# Precharge.net
KiCad netlist of a schematic drawn in Altium Designer
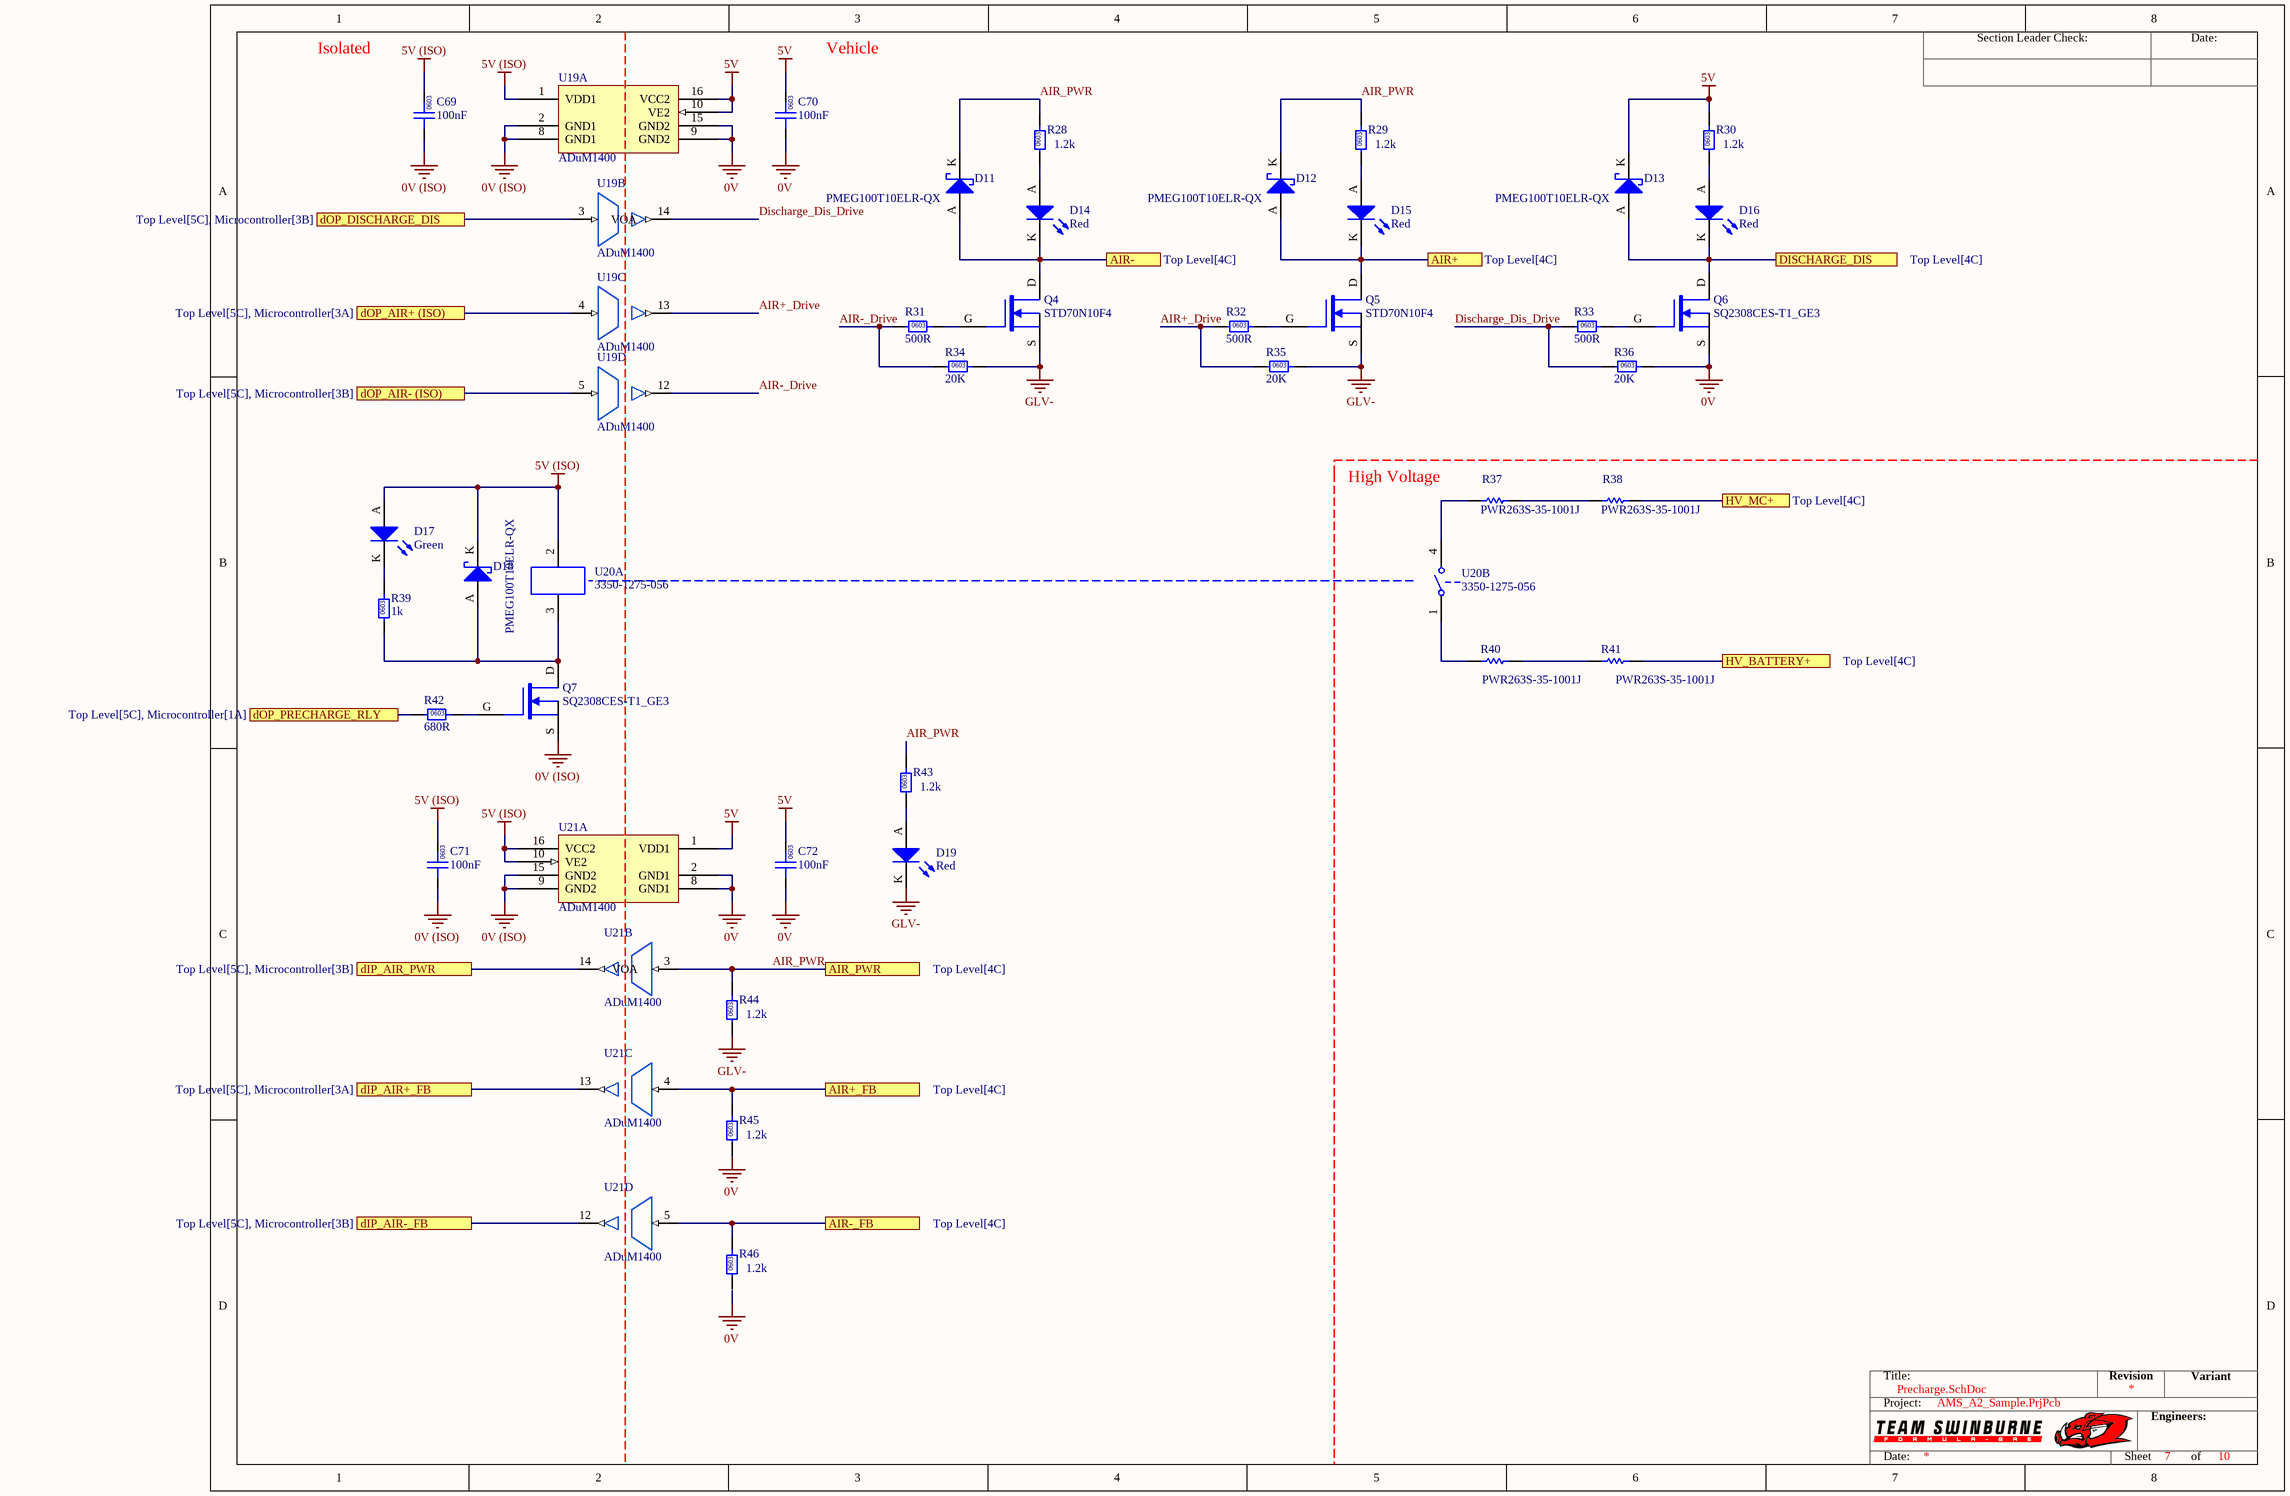
[diagram p0: Precharge.SchDoc]

(export (version "E")
  (design (tool "Eeschema 10.0.6"))
  (components
    (comp (ref "C69")
      (value "100nF")
      (footprint "0603")
      (fields
        (field (name "PART NUMBER") "GCM188L81H104KA57D")
        (field (name "MANUFACTURER") "muRata")
        (field (name "TOLERANCE") "±10%")
      )
      (libsource (lib "ts_standard_library") (part "Capacitor 0603"))
    )
    (comp (ref "C70")
      (value "100nF")
      (footprint "0603")
      (fields
        (field (name "PART NUMBER") "GCM188L81H104KA57D")
        (field (name "MANUFACTURER") "muRata")
        (field (name "TOLERANCE") "±10%")
      )
      (libsource (lib "ts_standard_library") (part "Capacitor 0603"))
    )
    (comp (ref "C71")
      (value "100nF")
      (footprint "0603")
      (fields
        (field (name "PART NUMBER") "GCM188L81H104KA57D")
        (field (name "MANUFACTURER") "muRata")
        (field (name "TOLERANCE") "±10%")
      )
      (libsource (lib "ts_standard_library") (part "Capacitor 0603"))
    )
    (comp (ref "C72")
      (value "100nF")
      (footprint "0603")
      (fields
        (field (name "PART NUMBER") "GCM188L81H104KA57D")
        (field (name "MANUFACTURER") "muRata")
        (field (name "TOLERANCE") "±10%")
      )
      (libsource (lib "ts_standard_library") (part "Capacitor 0603"))
    )
    (comp (ref "D11")
      (value "PMEG100T10ELR-QX")
      (footprint "NXP SOD123W")
      (fields
        (field (name "MANUFACTURER") "Nexperia USA Inc.")
        (field (name "DIGIKEY PART NUMBER") "1727-PMEG100T10ELR-QXCT-ND")
      )
      (libsource (lib "ts_standard_library") (part "Diode (Schottky)"))
    )
    (comp (ref "D12")
      (value "PMEG100T10ELR-QX")
      (footprint "NXP SOD123W")
      (fields
        (field (name "MANUFACTURER") "Nexperia USA Inc.")
        (field (name "DIGIKEY PART NUMBER") "1727-PMEG100T10ELR-QXCT-ND")
      )
      (libsource (lib "ts_standard_library") (part "Diode (Schottky)"))
    )
    (comp (ref "D13")
      (value "PMEG100T10ELR-QX")
      (footprint "NXP SOD123W")
      (fields
        (field (name "MANUFACTURER") "Nexperia USA Inc.")
        (field (name "DIGIKEY PART NUMBER") "1727-PMEG100T10ELR-QXCT-ND")
      )
      (libsource (lib "ts_standard_library") (part "Diode (Schottky)"))
    )
    (comp (ref "D14")
      (value "Red")
      (footprint "0805 LED")
      (description "Red LED Indication - Discrete 1.75V 0805 (2012 Metric)")
      (fields (field (name "PART NUMBER") "SML-210LTT86") (field (name "MANUFACTURER") "ROHM Semiconductor"))
      (libsource (lib "ts_standard_library") (part "LED"))
    )
    (comp (ref "D15")
      (value "Red")
      (footprint "0805 LED")
      (description "Red LED Indication - Discrete 1.75V 0805 (2012 Metric)")
      (fields (field (name "PART NUMBER") "SML-210LTT86") (field (name "MANUFACTURER") "ROHM Semiconductor"))
      (libsource (lib "ts_standard_library") (part "LED"))
    )
    (comp (ref "D16")
      (value "Red")
      (footprint "0805 LED")
      (description "Red LED Indication - Discrete 1.75V 0805 (2012 Metric)")
      (fields (field (name "PART NUMBER") "SML-210LTT86") (field (name "MANUFACTURER") "ROHM Semiconductor"))
      (libsource (lib "ts_standard_library") (part "LED"))
    )
    (comp (ref "D17")
      (value "Green")
      (footprint "0805 LED")
      (description "Green LED Indication - Discrete 1.75V 0805 (2012 Metric)")
      (fields (field (name "PART NUMBER") "SML-210FTT86") (field (name "MANUFACTURER") "ROHM Semiconductor"))
      (libsource (lib "ts_20-standard-library") (part "LED"))
    )
    (comp (ref "D18")
      (value "PMEG100T10ELR-QX")
      (footprint "NXP SOD123W")
      (fields
        (field (name "MANUFACTURER") "Nexperia USA Inc.")
        (field (name "DIGIKEY PART NUMBER") "1727-PMEG100T10ELR-QXCT-ND")
      )
      (libsource (lib "ts_standard_library") (part "Diode (Schottky)"))
    )
    (comp (ref "D19")
      (value "Red")
      (footprint "0805 LED")
      (description "Red LED Indication - Discrete 1.75V 0805 (2012 Metric)")
      (fields (field (name "PART NUMBER") "SML-210LTT86") (field (name "MANUFACTURER") "ROHM Semiconductor"))
      (libsource (lib "ts_standard_library") (part "LED"))
    )
    (comp (ref "Q4")
      (value "STD70N10F4")
      (footprint "STM TO-252 MOSFET")
      (description "N-Channel 100V 60A (Tc) 125W (Tc) Surface Mount DPAK")
      (fields
        (field (name "MANUFACTURER") "STMicroelectronics")
        (field (name "DIGIKEY PART NUMBER") "497-8806-2-ND")
        (field (name "PUBLISHER") "Altium Limited")
      )
      (libsource (lib "ts_standard_library") (part "MOSFET-N"))
    )
    (comp (ref "Q5")
      (value "STD70N10F4")
      (footprint "STM TO-252 MOSFET")
      (description "N-Channel 100V 60A (Tc) 125W (Tc) Surface Mount DPAK")
      (fields
        (field (name "MANUFACTURER") "STMicroelectronics")
        (field (name "DIGIKEY PART NUMBER") "497-8806-2-ND")
        (field (name "PUBLISHER") "Altium Limited")
      )
      (libsource (lib "ts_standard_library") (part "MOSFET-N"))
    )
    (comp (ref "Q6")
      (value "SQ2308CES-T1_GE3")
      (footprint "VSHY SOT-23-3")
      (description "MOSFET N-CH 60V 2.3A SOT23")
      (fields
        (field (name "MANUFACTURER") "Vishay Siliconix")
        (field (name "DIGIKEY PART NUMBER") "SQ2308CES-T1_GE3CT-ND")
        (field (name "PUBLISHER") "Altium Limited")
      )
      (libsource (lib "ts_standard_library") (part "MOSFET-N"))
    )
    (comp (ref "Q7")
      (value "SQ2308CES-T1_GE3")
      (footprint "VSHY SOT-23-3")
      (description "MOSFET N-CH 60V 2.3A SOT23")
      (fields
        (field (name "MANUFACTURER") "Vishay Siliconix")
        (field (name "DIGIKEY PART NUMBER") "SQ2308CES-T1_GE3CT-ND")
        (field (name "PUBLISHER") "Altium Limited")
      )
      (libsource (lib "ts_standard_library") (part "MOSFET-N"))
    )
    (comp (ref "R28")
      (value "1.2k")
      (footprint "0603")
      (fields
        (field (name "PART NUMBER") "RC0603JR-071K2L")
        (field (name "MANUFACTURER") "YAGEO")
        (field (name "TOLERANCE") "0.01")
      )
      (libsource (lib "ts_standard_library") (part "Resistor 0603"))
    )
    (comp (ref "R29")
      (value "1.2k")
      (footprint "0603")
      (fields
        (field (name "PART NUMBER") "RC0603JR-071K2L")
        (field (name "MANUFACTURER") "YAGEO")
        (field (name "TOLERANCE") "0.01")
      )
      (libsource (lib "ts_standard_library") (part "Resistor 0603"))
    )
    (comp (ref "R30")
      (value "1.2k")
      (footprint "0603")
      (fields
        (field (name "PART NUMBER") "RC0603JR-071K2L")
        (field (name "MANUFACTURER") "YAGEO")
        (field (name "TOLERANCE") "0.01")
      )
      (libsource (lib "ts_standard_library") (part "Resistor 0603"))
    )
    (comp (ref "R31")
      (value "500R")
      (footprint "0603")
      (fields
        (field (name "PART NUMBER") "RT0603BRD07500RL")
        (field (name "MANUFACTURER") "YAGEO")
        (field (name "TOLERANCE") "0.01")
      )
      (libsource (lib "ts_standard_library") (part "Resistor 0603"))
    )
    (comp (ref "R32")
      (value "500R")
      (footprint "0603")
      (fields
        (field (name "PART NUMBER") "RT0603BRD07500RL")
        (field (name "MANUFACTURER") "YAGEO")
        (field (name "TOLERANCE") "0.01")
      )
      (libsource (lib "ts_standard_library") (part "Resistor 0603"))
    )
    (comp (ref "R33")
      (value "500R")
      (footprint "0603")
      (fields
        (field (name "PART NUMBER") "RT0603BRD07500RL")
        (field (name "MANUFACTURER") "YAGEO")
        (field (name "TOLERANCE") "0.01")
      )
      (libsource (lib "ts_standard_library") (part "Resistor 0603"))
    )
    (comp (ref "R34")
      (value "20K")
      (footprint "0603")
      (fields
        (field (name "PART NUMBER") "RC0603FR-0720KL")
        (field (name "MANUFACTURER") "YAGEO")
        (field (name "TOLERANCE") "0.01")
      )
      (libsource (lib "ts_standard_library") (part "Resistor 0603"))
    )
    (comp (ref "R35")
      (value "20K")
      (footprint "0603")
      (fields
        (field (name "PART NUMBER") "RC0603FR-0720KL")
        (field (name "MANUFACTURER") "YAGEO")
        (field (name "TOLERANCE") "0.01")
      )
      (libsource (lib "ts_standard_library") (part "Resistor 0603"))
    )
    (comp (ref "R36")
      (value "20K")
      (footprint "0603")
      (fields
        (field (name "PART NUMBER") "RC0603FR-0720KL")
        (field (name "MANUFACTURER") "YAGEO")
        (field (name "TOLERANCE") "0.01")
      )
      (libsource (lib "ts_standard_library") (part "Resistor 0603"))
    )
    (comp (ref "R37")
      (value "PWR263S-35-1001J")
      (footprint "B TO-263")
      (fields
        (field (name "MANUFACTURER") "Bournes Inc")
        (field (name "TOLERANCE") "0.05")
        (field (name "DIGIKEY PART NUMBER") "PWR263S-35-1001J-ND")
      )
      (libsource (lib "Team Swinburne") (part "Resistor"))
    )
    (comp (ref "R38")
      (value "PWR263S-35-1001J")
      (footprint "B TO-263")
      (fields
        (field (name "MANUFACTURER") "Bournes Inc")
        (field (name "TOLERANCE") "0.05")
        (field (name "DIGIKEY PART NUMBER") "PWR263S-35-1001J-ND")
      )
      (libsource (lib "Team Swinburne") (part "Resistor"))
    )
    (comp (ref "R39")
      (value "1k")
      (footprint "0603")
      (fields
        (field (name "PART NUMBER") "RC0603FR-071KL")
        (field (name "MANUFACTURER") "YAGEO")
        (field (name "TOLERANCE") "0.01")
      )
      (libsource (lib "ts_standard_library") (part "Resistor 0603"))
    )
    (comp (ref "R40")
      (value "PWR263S-35-1001J")
      (footprint "B TO-263")
      (fields
        (field (name "MANUFACTURER") "Bournes Inc")
        (field (name "TOLERANCE") "0.05")
        (field (name "DIGIKEY PART NUMBER") "PWR263S-35-1001J-ND")
      )
      (libsource (lib "Team Swinburne") (part "Resistor"))
    )
    (comp (ref "R41")
      (value "PWR263S-35-1001J")
      (footprint "B TO-263")
      (fields
        (field (name "MANUFACTURER") "Bournes Inc")
        (field (name "TOLERANCE") "0.05")
        (field (name "DIGIKEY PART NUMBER") "PWR263S-35-1001J-ND")
      )
      (libsource (lib "Team Swinburne") (part "Resistor"))
    )
    (comp (ref "R42")
      (value "680R")
      (footprint "0603")
      (fields
        (field (name "PART NUMBER") "RC0603JR-13680RL")
        (field (name "MANUFACTURER") "YAGEO")
        (field (name "TOLERANCE") "0.01")
      )
      (libsource (lib "ts_standard_library") (part "Resistor 0603"))
    )
    (comp (ref "R43")
      (value "1.2k")
      (footprint "0603")
      (fields
        (field (name "PART NUMBER") "RC0603JR-071K2L")
        (field (name "MANUFACTURER") "YAGEO")
        (field (name "TOLERANCE") "0.01")
      )
      (libsource (lib "ts_standard_library") (part "Resistor 0603"))
    )
    (comp (ref "R44")
      (value "1.2k")
      (footprint "0603")
      (fields
        (field (name "PART NUMBER") "RC0603JR-071K2L")
        (field (name "MANUFACTURER") "YAGEO")
        (field (name "TOLERANCE") "0.01")
      )
      (libsource (lib "ts_standard_library") (part "Resistor 0603"))
    )
    (comp (ref "R45")
      (value "1.2k")
      (footprint "0603")
      (fields
        (field (name "PART NUMBER") "RC0603JR-071K2L")
        (field (name "MANUFACTURER") "YAGEO")
        (field (name "TOLERANCE") "0.01")
      )
      (libsource (lib "ts_standard_library") (part "Resistor 0603"))
    )
    (comp (ref "R46")
      (value "1.2k")
      (footprint "0603")
      (fields
        (field (name "PART NUMBER") "RC0603JR-071K2L")
        (field (name "MANUFACTURER") "YAGEO")
        (field (name "TOLERANCE") "0.01")
      )
      (libsource (lib "ts_standard_library") (part "Resistor 0603"))
    )
    (comp (ref "U19")
      (value "ADuM1400")
      (footprint "AD 16-SOIC")
      (fields
        (field (name "MANUFACTURER") "Analog Devices")
        (field (name "DIGIKEY PART NUMBER") "ADUM1400WSRWZ-ND")
      )
      (libsource (lib "") (part "ADuM1400_1"))
    )
    (comp (ref "U20")
      (value "3350-1275-056")
      (footprint "CI SPST")
      (description "RELAY REED HV SPST 200W 3A 5V (NO)")
      (fields
        (field (name "MANUFACTURER") "Comus International")
        (field (name "DIGIKEY PART NUMBER") "1835-1036-ND")
      )
      (libsource (lib "ts_standard_library") (part "3350-1275-056"))
    )
    (comp (ref "U21")
      (value "ADuM1400")
      (footprint "AD 16-SOIC")
      (fields
        (field (name "MANUFACTURER") "Analog Devices")
        (field (name "DIGIKEY PART NUMBER") "ADUM1400WSRWZ-ND")
      )
      (libsource (lib "ts_standard_library") (part "ADuM1400"))
    )
  )
  (nets
    (net (code "1") (name "/AIR+") (class "Default")
      (node (ref "D12") (pin "A") (pinfunction "A_A") (pintype "passive"))
      (node (ref "D15") (pin "K") (pinfunction "K_K") (pintype "passive"))
      (node (ref "Q5") (pin "D") (pinfunction "D_D") (pintype "passive"))
    )
    (net (code "2") (name "/AIR+_Drive") (class "Default")
      (node (ref "R32") (pin "1") (pinfunction "1_1") (pintype "passive"))
      (node (ref "R35") (pin "1") (pinfunction "1_1") (pintype "passive"))
      (node (ref "U19") (pin "13") (pinfunction "VOB_13") (pintype "output"))
    )
    (net (code "3") (name "/AIR+_FB") (class "Default")
      (node (ref "R45") (pin "2") (pinfunction "2_2") (pintype "passive"))
      (node (ref "U21") (pin "4") (pinfunction "VIB_4") (pintype "input"))
    )
    (net (code "4") (name "/AIR-") (class "Default")
      (node (ref "D11") (pin "A") (pinfunction "A_A") (pintype "passive"))
      (node (ref "D14") (pin "K") (pinfunction "K_K") (pintype "passive"))
      (node (ref "Q4") (pin "D") (pinfunction "D_D") (pintype "passive"))
    )
    (net (code "5") (name "/AIR-_Drive") (class "Default")
      (node (ref "R31") (pin "1") (pinfunction "1_1") (pintype "passive"))
      (node (ref "R34") (pin "1") (pinfunction "1_1") (pintype "passive"))
      (node (ref "U19") (pin "12") (pinfunction "VOC_12") (pintype "output"))
    )
    (net (code "6") (name "/AIR-_FB") (class "Default")
      (node (ref "R46") (pin "2") (pinfunction "2_2") (pintype "passive"))
      (node (ref "U21") (pin "5") (pinfunction "VIC_5") (pintype "input"))
    )
    (net (code "7") (name "/AIR_PWR") (class "Default")
      (node (ref "D11") (pin "K") (pinfunction "K_K") (pintype "passive"))
      (node (ref "D12") (pin "K") (pinfunction "K_K") (pintype "passive"))
      (node (ref "R28") (pin "2") (pinfunction "2_2") (pintype "passive"))
      (node (ref "R29") (pin "2") (pinfunction "2_2") (pintype "passive"))
      (node (ref "R43") (pin "2") (pinfunction "2_2") (pintype "passive"))
      (node (ref "R44") (pin "2") (pinfunction "2_2") (pintype "passive"))
      (node (ref "U21") (pin "3") (pinfunction "VIA_3") (pintype "input"))
    )
    (net (code "8") (name "/DISCHARGE_DIS") (class "Default")
      (node (ref "D13") (pin "A") (pinfunction "A_A") (pintype "passive"))
      (node (ref "D16") (pin "K") (pinfunction "K_K") (pintype "passive"))
      (node (ref "Q6") (pin "D") (pinfunction "D_D") (pintype "passive"))
    )
    (net (code "9") (name "/Discharge_Dis_Drive") (class "Default")
      (node (ref "R33") (pin "1") (pinfunction "1_1") (pintype "passive"))
      (node (ref "R36") (pin "1") (pinfunction "1_1") (pintype "passive"))
      (node (ref "U19") (pin "14") (pinfunction "VOA_14") (pintype "output"))
    )
    (net (code "10") (name "/HV_BATTERY+") (class "Default")
      (node (ref "R41") (pin "1") (pinfunction "1_1") (pintype "passive"))
    )
    (net (code "11") (name "/HV_MC+") (class "Default")
      (node (ref "R38") (pin "2") (pinfunction "2_2") (pintype "passive"))
    )
    (net (code "12") (name "/dIP_AIR+_FB") (class "Default")
      (node (ref "U21") (pin "13") (pinfunction "VOB_13") (pintype "output"))
    )
    (net (code "13") (name "/dIP_AIR-_FB") (class "Default")
      (node (ref "U21") (pin "12") (pinfunction "VOC_12") (pintype "output"))
    )
    (net (code "14") (name "/dIP_AIR_PWR") (class "Default")
      (node (ref "U21") (pin "14") (pinfunction "VOA_14") (pintype "output"))
    )
    (net (code "15") (name "/dOP_AIR+ (ISO)") (class "Default")
      (node (ref "U19") (pin "4") (pinfunction "VIB_4") (pintype "input"))
    )
    (net (code "16") (name "/dOP_AIR- (ISO)") (class "Default")
      (node (ref "U19") (pin "5") (pinfunction "VIC_5") (pintype "input"))
    )
    (net (code "17") (name "/dOP_DISCHARGE_DIS") (class "Default")
      (node (ref "U19") (pin "3") (pinfunction "VIA_3") (pintype "input"))
    )
    (net (code "18") (name "/dOP_PRECHARGE_RLY") (class "Default")
      (node (ref "R42") (pin "1") (pinfunction "1_1") (pintype "passive"))
    )
    (net (code "19") (name "0V") (class "Default")
      (node (ref "C70") (pin "1") (pinfunction "1_1") (pintype "passive"))
      (node (ref "C72") (pin "1") (pinfunction "1_1") (pintype "passive"))
      (node (ref "Q6") (pin "S") (pinfunction "S_S") (pintype "passive"))
      (node (ref "R36") (pin "2") (pinfunction "2_2") (pintype "passive"))
      (node (ref "R45") (pin "1") (pinfunction "1_1") (pintype "passive"))
      (node (ref "U19") (pin "15") (pinfunction "GND2_15") (pintype "power_in"))
      (node (ref "U19") (pin "9") (pinfunction "GND2_9") (pintype "power_in"))
      (node (ref "U21") (pin "2") (pinfunction "GND1_2") (pintype "power_in"))
      (node (ref "U21") (pin "8") (pinfunction "GND1_8") (pintype "power_in"))
    )
    (net (code "20") (name "0V (ISO)") (class "Default")
      (node (ref "C69") (pin "1") (pinfunction "1_1") (pintype "passive"))
      (node (ref "C71") (pin "1") (pinfunction "1_1") (pintype "passive"))
      (node (ref "Q7") (pin "S") (pinfunction "S_S") (pintype "passive"))
      (node (ref "U19") (pin "2") (pinfunction "GND1_2") (pintype "power_in"))
      (node (ref "U19") (pin "8") (pinfunction "GND1_8") (pintype "power_in"))
      (node (ref "U21") (pin "15") (pinfunction "GND2_15") (pintype "power_in"))
      (node (ref "U21") (pin "9") (pinfunction "GND2_9") (pintype "power_in"))
    )
    (net (code "21") (name "5V") (class "Default")
      (node (ref "C70") (pin "2") (pinfunction "2_2") (pintype "passive"))
      (node (ref "C72") (pin "2") (pinfunction "2_2") (pintype "passive"))
      (node (ref "D13") (pin "K") (pinfunction "K_K") (pintype "passive"))
      (node (ref "R30") (pin "2") (pinfunction "2_2") (pintype "passive"))
      (node (ref "U19") (pin "10") (pinfunction "VE2_10") (pintype "input"))
      (node (ref "U19") (pin "16") (pinfunction "VCC2_16") (pintype "power_in"))
      (node (ref "U21") (pin "1") (pinfunction "VDD1_1") (pintype "power_in"))
    )
    (net (code "22") (name "5V (ISO)") (class "Default")
      (node (ref "C69") (pin "2") (pinfunction "2_2") (pintype "passive"))
      (node (ref "C71") (pin "2") (pinfunction "2_2") (pintype "passive"))
      (node (ref "D17") (pin "A") (pinfunction "A_A") (pintype "passive"))
      (node (ref "D18") (pin "K") (pinfunction "K_K") (pintype "passive"))
      (node (ref "U19") (pin "1") (pinfunction "VDD1_1") (pintype "power_in"))
      (node (ref "U20") (pin "2") (pinfunction "2_2") (pintype "passive"))
      (node (ref "U21") (pin "10") (pinfunction "VE2_10") (pintype "input"))
      (node (ref "U21") (pin "16") (pinfunction "VCC2_16") (pintype "power_in"))
    )
    (net (code "23") (name "GLV-") (class "Default")
      (node (ref "D19") (pin "K") (pinfunction "K_K") (pintype "passive"))
      (node (ref "Q4") (pin "S") (pinfunction "S_S") (pintype "passive"))
      (node (ref "Q5") (pin "S") (pinfunction "S_S") (pintype "passive"))
      (node (ref "R34") (pin "2") (pinfunction "2_2") (pintype "passive"))
      (node (ref "R35") (pin "2") (pinfunction "2_2") (pintype "passive"))
      (node (ref "R44") (pin "1") (pinfunction "1_1") (pintype "passive"))
    )
    (net (code "24") (name "Net-(D14-PadA)") (class "Default")
      (node (ref "D14") (pin "A") (pinfunction "A_A") (pintype "passive"))
      (node (ref "R28") (pin "1") (pinfunction "1_1") (pintype "passive"))
    )
    (net (code "25") (name "Net-(D15-PadA)") (class "Default")
      (node (ref "D15") (pin "A") (pinfunction "A_A") (pintype "passive"))
      (node (ref "R29") (pin "1") (pinfunction "1_1") (pintype "passive"))
    )
    (net (code "26") (name "Net-(D16-PadA)") (class "Default")
      (node (ref "D16") (pin "A") (pinfunction "A_A") (pintype "passive"))
      (node (ref "R30") (pin "1") (pinfunction "1_1") (pintype "passive"))
    )
    (net (code "27") (name "Net-(D17-PadK)") (class "Default")
      (node (ref "D17") (pin "K") (pinfunction "K_K") (pintype "passive"))
      (node (ref "R39") (pin "2") (pinfunction "2_2") (pintype "passive"))
    )
    (net (code "28") (name "Net-(D18-PadA)") (class "Default")
      (node (ref "D18") (pin "A") (pinfunction "A_A") (pintype "passive"))
      (node (ref "Q7") (pin "D") (pinfunction "D_D") (pintype "passive"))
      (node (ref "R39") (pin "1") (pinfunction "1_1") (pintype "passive"))
      (node (ref "U20") (pin "3") (pinfunction "3_3") (pintype "passive"))
    )
    (net (code "29") (name "Net-(D19-PadA)") (class "Default")
      (node (ref "D19") (pin "A") (pinfunction "A_A") (pintype "passive"))
      (node (ref "R43") (pin "1") (pinfunction "1_1") (pintype "passive"))
    )
    (net (code "30") (name "Net-(Q4-PadG)") (class "Default")
      (node (ref "Q4") (pin "G") (pinfunction "G_G") (pintype "passive"))
      (node (ref "R31") (pin "2") (pinfunction "2_2") (pintype "passive"))
    )
    (net (code "31") (name "Net-(Q5-PadG)") (class "Default")
      (node (ref "Q5") (pin "G") (pinfunction "G_G") (pintype "passive"))
      (node (ref "R32") (pin "2") (pinfunction "2_2") (pintype "passive"))
    )
    (net (code "32") (name "Net-(Q6-PadG)") (class "Default")
      (node (ref "Q6") (pin "G") (pinfunction "G_G") (pintype "passive"))
      (node (ref "R33") (pin "2") (pinfunction "2_2") (pintype "passive"))
    )
    (net (code "33") (name "Net-(Q7-PadG)") (class "Default")
      (node (ref "Q7") (pin "G") (pinfunction "G_G") (pintype "passive"))
      (node (ref "R42") (pin "2") (pinfunction "2_2") (pintype "passive"))
    )
    (net (code "34") (name "Net-(R37-Pad1)") (class "Default")
      (node (ref "R37") (pin "1") (pinfunction "1_1") (pintype "passive"))
      (node (ref "U20") (pin "4") (pinfunction "4_4") (pintype "passive"))
    )
    (net (code "35") (name "Net-(R37-Pad2)") (class "Default")
      (node (ref "R37") (pin "2") (pinfunction "2_2") (pintype "passive"))
      (node (ref "R38") (pin "1") (pinfunction "1_1") (pintype "passive"))
    )
    (net (code "36") (name "Net-(R40-Pad1)") (class "Default")
      (node (ref "R40") (pin "1") (pinfunction "1_1") (pintype "passive"))
      (node (ref "R41") (pin "2") (pinfunction "2_2") (pintype "passive"))
    )
    (net (code "37") (name "Net-(R40-Pad2)") (class "Default")
      (node (ref "R40") (pin "2") (pinfunction "2_2") (pintype "passive"))
      (node (ref "U20") (pin "1") (pinfunction "1_1") (pintype "passive"))
    )
    (net (code "38") (name "unconnected-(R46-Pad1)") (class "Default")
      (node (ref "R46") (pin "1") (pinfunction "1_1") (pintype "passive"))
    )
  )
)
